# ddr3.net
KiCad netlist of a schematic drawn in Altium Designer
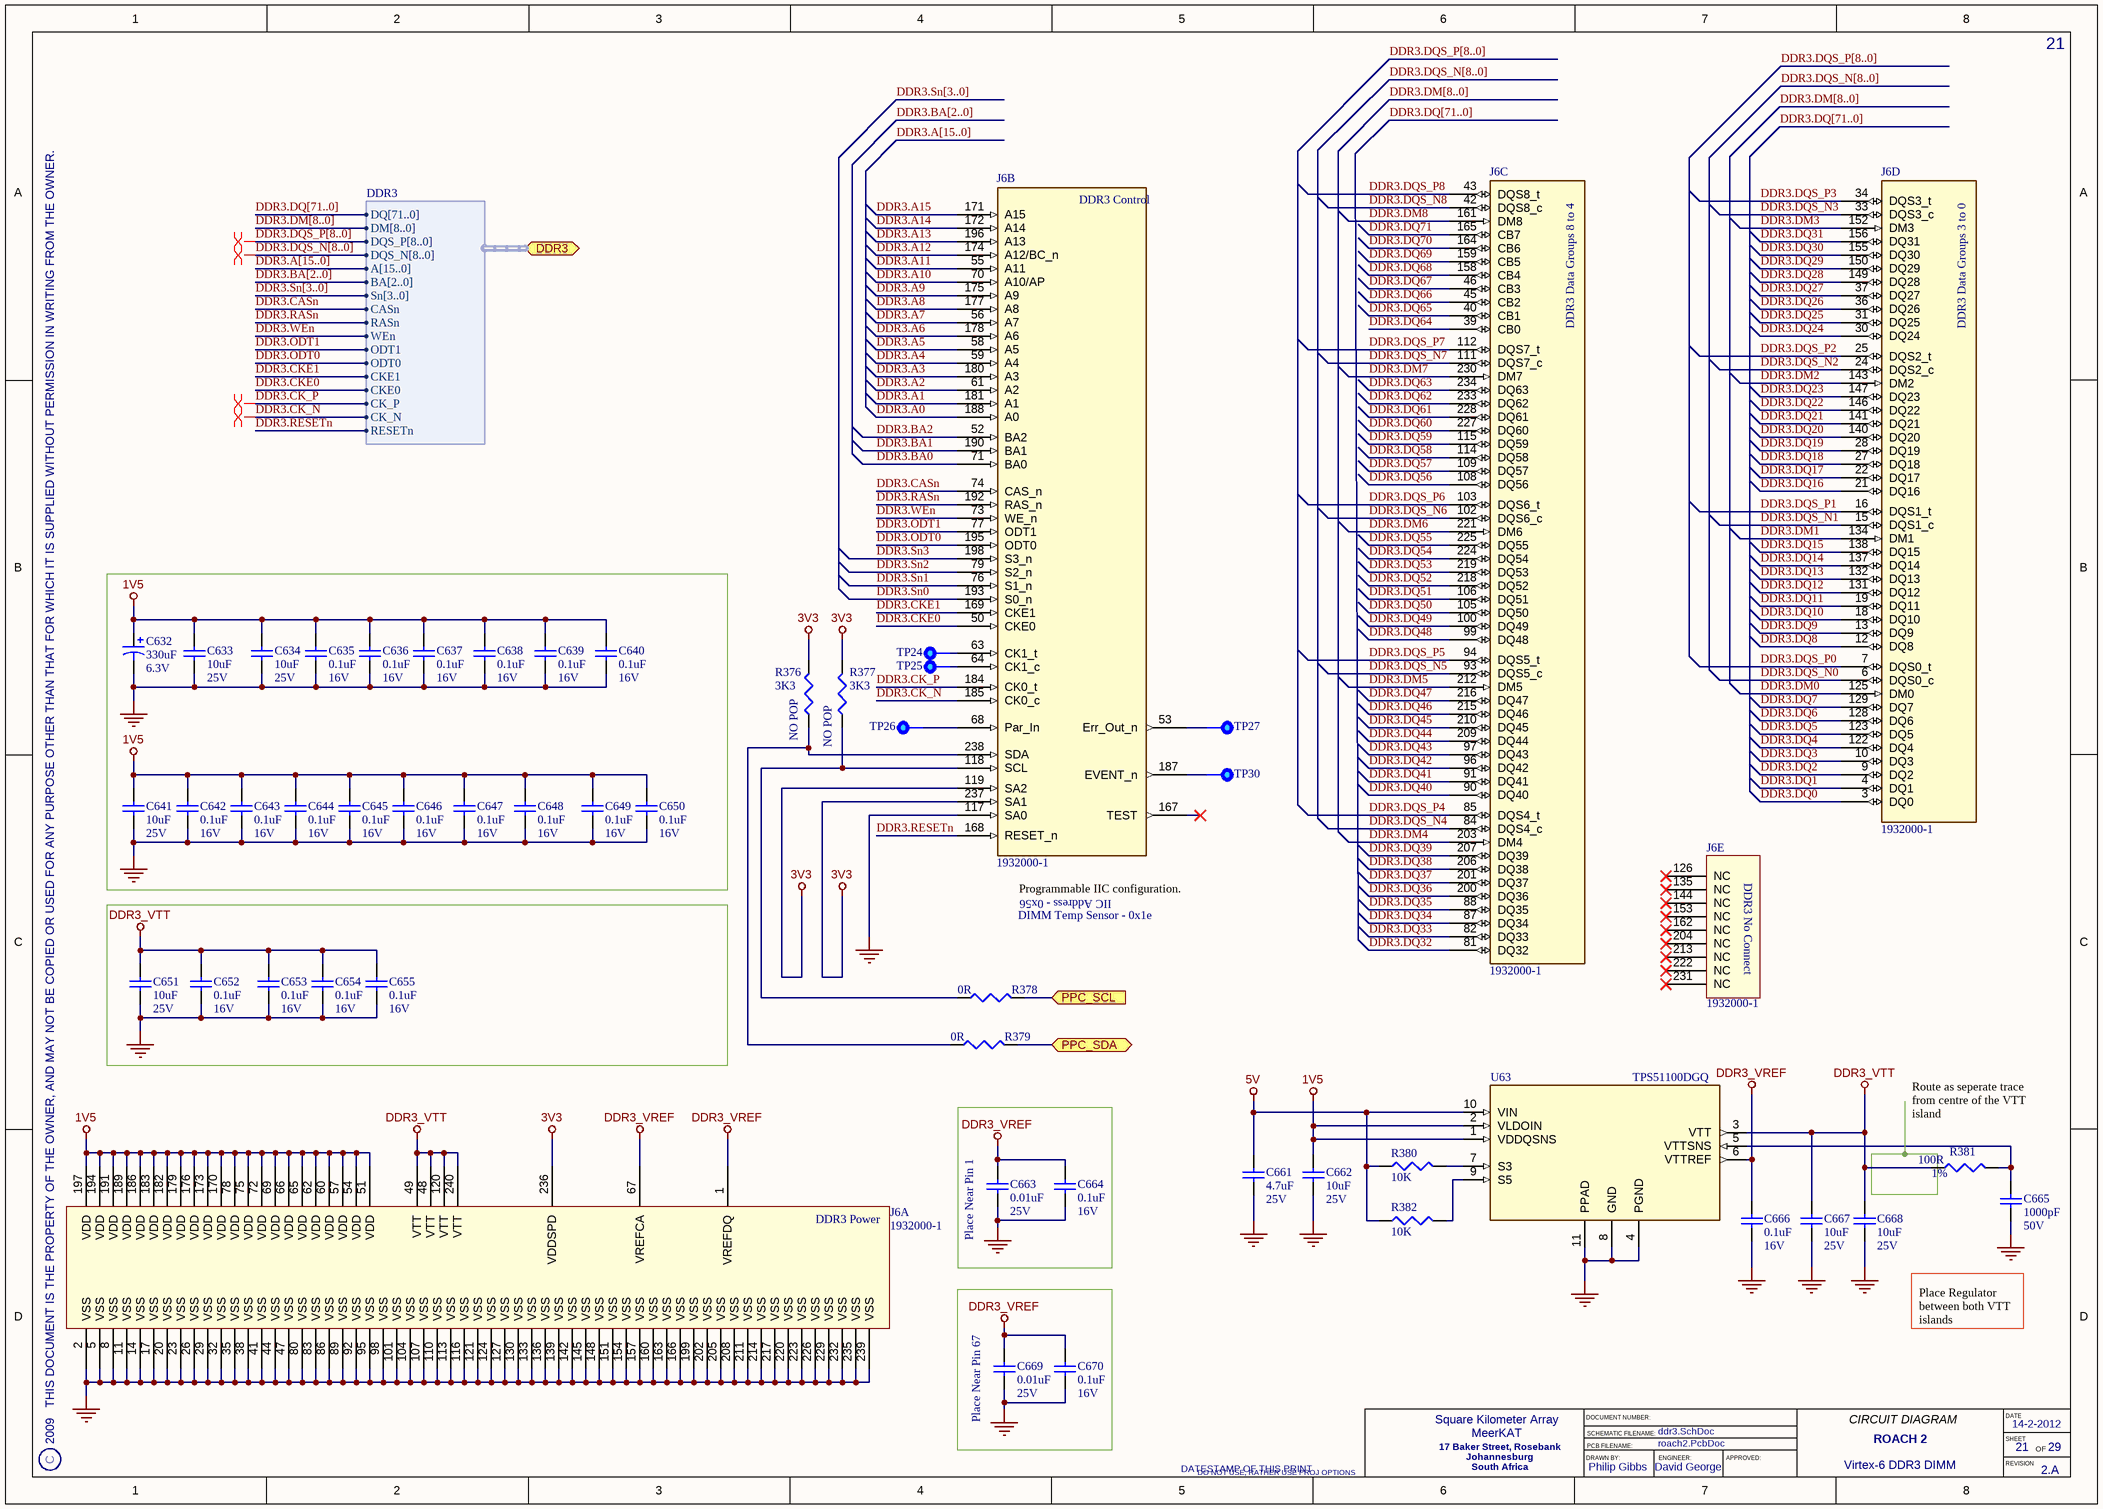
[diagram p0: ddr3.SchDoc]

(export (version "E")
  (design (tool "Eeschema 10.0.6"))
  (components
    (comp (ref "C632")
      (value "330uF")
      (footprint "CAPMP7343X280L")
      (description "330uF, Conductive Polymer Chip Capacitor")
      (fields
        (field (name "RATING") "6.3V")
        (field (name "MANUFACTURER") "KEMET")
        (field (name "PARTNUM") "T520D337M006ATE045")
      )
      (libsource (lib "altium_db") (part "CapPol"))
    )
    (comp (ref "C633")
      (value "10uF")
      (footprint "CAPC3225X200L")
      (description "10uF, Ceramic Capacitor")
      (fields
        (field (name "RATING") "25V")
        (field (name "MANUFACTURER") "MURATA")
        (field (name "PARTNUM") "GRM32DR61E106KA12L")
      )
      (libsource (lib "altium_db") (part "CapStd"))
    )
    (comp (ref "C634")
      (value "10uF")
      (footprint "CAPC3225X200L")
      (description "10uF, Ceramic Capacitor")
      (fields
        (field (name "RATING") "25V")
        (field (name "MANUFACTURER") "MURATA")
        (field (name "PARTNUM") "GRM32DR61E106KA12L")
      )
      (libsource (lib "altium_db") (part "CapStd"))
    )
    (comp (ref "C635")
      (value "0.1uF")
      (footprint "CAPC1005X60L")
      (description "0.1uF, Ceramic Capacitor")
      (fields
        (field (name "RATING") "16V")
        (field (name "MANUFACTURER") "VENKEL")
        (field (name "PARTNUM") "C0402X7R160-104KN")
      )
      (libsource (lib "altium_db") (part "CapStd"))
    )
    (comp (ref "C636")
      (value "0.1uF")
      (footprint "CAPC1005X60L")
      (description "0.1uF, Ceramic Capacitor")
      (fields
        (field (name "RATING") "16V")
        (field (name "MANUFACTURER") "VENKEL")
        (field (name "PARTNUM") "C0402X7R160-104KN")
      )
      (libsource (lib "altium_db") (part "CapStd"))
    )
    (comp (ref "C637")
      (value "0.1uF")
      (footprint "CAPC1005X60L")
      (description "0.1uF, Ceramic Capacitor")
      (fields
        (field (name "RATING") "16V")
        (field (name "MANUFACTURER") "VENKEL")
        (field (name "PARTNUM") "C0402X7R160-104KN")
      )
      (libsource (lib "altium_db") (part "CapStd"))
    )
    (comp (ref "C638")
      (value "0.1uF")
      (footprint "CAPC1005X60L")
      (description "0.1uF, Ceramic Capacitor")
      (fields
        (field (name "RATING") "16V")
        (field (name "MANUFACTURER") "VENKEL")
        (field (name "PARTNUM") "C0402X7R160-104KN")
      )
      (libsource (lib "altium_db") (part "CapStd"))
    )
    (comp (ref "C639")
      (value "0.1uF")
      (footprint "CAPC1005X60L")
      (description "0.1uF, Ceramic Capacitor")
      (fields
        (field (name "RATING") "16V")
        (field (name "MANUFACTURER") "VENKEL")
        (field (name "PARTNUM") "C0402X7R160-104KN")
      )
      (libsource (lib "altium_db") (part "CapStd"))
    )
    (comp (ref "C640")
      (value "0.1uF")
      (footprint "CAPC1005X60L")
      (description "0.1uF, Ceramic Capacitor")
      (fields
        (field (name "RATING") "16V")
        (field (name "MANUFACTURER") "VENKEL")
        (field (name "PARTNUM") "C0402X7R160-104KN")
      )
      (libsource (lib "altium_db") (part "CapStd"))
    )
    (comp (ref "C641")
      (value "10uF")
      (footprint "CAPC3225X200L")
      (description "10uF, Ceramic Capacitor")
      (fields
        (field (name "RATING") "25V")
        (field (name "MANUFACTURER") "MURATA")
        (field (name "PARTNUM") "GRM32DR61E106KA12L")
      )
      (libsource (lib "altium_db") (part "CapStd"))
    )
    (comp (ref "C642")
      (value "0.1uF")
      (footprint "CAPC1005X60L")
      (description "0.1uF, Ceramic Capacitor")
      (fields
        (field (name "RATING") "16V")
        (field (name "MANUFACTURER") "VENKEL")
        (field (name "PARTNUM") "C0402X7R160-104KN")
      )
      (libsource (lib "altium_db") (part "CapStd"))
    )
    (comp (ref "C643")
      (value "0.1uF")
      (footprint "CAPC1005X60L")
      (description "0.1uF, Ceramic Capacitor")
      (fields
        (field (name "RATING") "16V")
        (field (name "MANUFACTURER") "VENKEL")
        (field (name "PARTNUM") "C0402X7R160-104KN")
      )
      (libsource (lib "altium_db") (part "CapStd"))
    )
    (comp (ref "C644")
      (value "0.1uF")
      (footprint "CAPC1005X60L")
      (description "0.1uF, Ceramic Capacitor")
      (fields
        (field (name "RATING") "16V")
        (field (name "MANUFACTURER") "VENKEL")
        (field (name "PARTNUM") "C0402X7R160-104KN")
      )
      (libsource (lib "altium_db") (part "CapStd"))
    )
    (comp (ref "C645")
      (value "0.1uF")
      (footprint "CAPC1005X60L")
      (description "0.1uF, Ceramic Capacitor")
      (fields
        (field (name "RATING") "16V")
        (field (name "MANUFACTURER") "VENKEL")
        (field (name "PARTNUM") "C0402X7R160-104KN")
      )
      (libsource (lib "altium_db") (part "CapStd"))
    )
    (comp (ref "C646")
      (value "0.1uF")
      (footprint "CAPC1005X60L")
      (description "0.1uF, Ceramic Capacitor")
      (fields
        (field (name "RATING") "16V")
        (field (name "MANUFACTURER") "VENKEL")
        (field (name "PARTNUM") "C0402X7R160-104KN")
      )
      (libsource (lib "altium_db") (part "CapStd"))
    )
    (comp (ref "C647")
      (value "0.1uF")
      (footprint "CAPC1005X60L")
      (description "0.1uF, Ceramic Capacitor")
      (fields
        (field (name "RATING") "16V")
        (field (name "MANUFACTURER") "VENKEL")
        (field (name "PARTNUM") "C0402X7R160-104KN")
      )
      (libsource (lib "altium_db") (part "CapStd"))
    )
    (comp (ref "C648")
      (value "0.1uF")
      (footprint "CAPC1005X60L")
      (description "0.1uF, Ceramic Capacitor")
      (fields
        (field (name "RATING") "16V")
        (field (name "MANUFACTURER") "VENKEL")
        (field (name "PARTNUM") "C0402X7R160-104KN")
      )
      (libsource (lib "altium_db") (part "CapStd"))
    )
    (comp (ref "C649")
      (value "0.1uF")
      (footprint "CAPC1005X60L")
      (description "0.1uF, Ceramic Capacitor")
      (fields
        (field (name "RATING") "16V")
        (field (name "MANUFACTURER") "VENKEL")
        (field (name "PARTNUM") "C0402X7R160-104KN")
      )
      (libsource (lib "altium_db") (part "CapStd"))
    )
    (comp (ref "C650")
      (value "0.1uF")
      (footprint "CAPC1005X60L")
      (description "0.1uF, Ceramic Capacitor")
      (fields
        (field (name "RATING") "16V")
        (field (name "MANUFACTURER") "VENKEL")
        (field (name "PARTNUM") "C0402X7R160-104KN")
      )
      (libsource (lib "altium_db") (part "CapStd"))
    )
    (comp (ref "C651")
      (value "10uF")
      (footprint "CAPC3225X200L")
      (description "10uF, Ceramic Capacitor")
      (fields
        (field (name "RATING") "25V")
        (field (name "MANUFACTURER") "MURATA")
        (field (name "PARTNUM") "GRM32DR61E106KA12L")
      )
      (libsource (lib "altium_db") (part "CapStd"))
    )
    (comp (ref "C652")
      (value "0.1uF")
      (footprint "CAPC1005X60L")
      (description "0.1uF, Ceramic Capacitor")
      (fields
        (field (name "RATING") "16V")
        (field (name "MANUFACTURER") "VENKEL")
        (field (name "PARTNUM") "C0402X7R160-104KN")
      )
      (libsource (lib "altium_db") (part "CapStd"))
    )
    (comp (ref "C653")
      (value "0.1uF")
      (footprint "CAPC1005X60L")
      (description "0.1uF, Ceramic Capacitor")
      (fields
        (field (name "RATING") "16V")
        (field (name "MANUFACTURER") "VENKEL")
        (field (name "PARTNUM") "C0402X7R160-104KN")
      )
      (libsource (lib "altium_db") (part "CapStd"))
    )
    (comp (ref "C654")
      (value "0.1uF")
      (footprint "CAPC1005X60L")
      (description "0.1uF, Ceramic Capacitor")
      (fields
        (field (name "RATING") "16V")
        (field (name "MANUFACTURER") "VENKEL")
        (field (name "PARTNUM") "C0402X7R160-104KN")
      )
      (libsource (lib "altium_db") (part "CapStd"))
    )
    (comp (ref "C655")
      (value "0.1uF")
      (footprint "CAPC1005X60L")
      (description "0.1uF, Ceramic Capacitor")
      (fields
        (field (name "RATING") "16V")
        (field (name "MANUFACTURER") "VENKEL")
        (field (name "PARTNUM") "C0402X7R160-104KN")
      )
      (libsource (lib "altium_db") (part "CapStd"))
    )
    (comp (ref "C661")
      (value "4.7uF")
      (footprint "CAPC2012X127L")
      (description "4.7uF, Ceramic Capacitor")
      (fields
        (field (name "RATING") "25V")
        (field (name "MANUFACTURER") "MURATA")
        (field (name "PARTNUM") "GRM21BR61E475KA12K")
      )
      (libsource (lib "altium_db") (part "CapStd"))
    )
    (comp (ref "C662")
      (value "10uF")
      (footprint "CAPC3225X200L")
      (description "10uF, Ceramic Capacitor")
      (fields
        (field (name "RATING") "25V")
        (field (name "MANUFACTURER") "MURATA")
        (field (name "PARTNUM") "GRM32DR61E106KA12L")
      )
      (libsource (lib "altium_db") (part "CapStd"))
    )
    (comp (ref "C663")
      (value "0.01uF")
      (footprint "CAPC1005X55L")
      (description "0.01uF, Ceramic Capacitor")
      (fields
        (field (name "RATING") "25V")
        (field (name "MANUFACTURER") "MURATA")
        (field (name "PARTNUM") "GRM155R71E103KA01D")
      )
      (libsource (lib "altium_db") (part "CapStd"))
    )
    (comp (ref "C664")
      (value "0.1uF")
      (footprint "CAPC1005X60L")
      (description "0.1uF, Ceramic Capacitor")
      (fields
        (field (name "RATING") "16V")
        (field (name "MANUFACTURER") "VENKEL")
        (field (name "PARTNUM") "C0402X7R160-104KN")
      )
      (libsource (lib "altium_db") (part "CapStd"))
    )
    (comp (ref "C665")
      (value "1000pF")
      (footprint "CAPC1005X55L")
      (description "1000pF, Ceramic Capacitor")
      (fields
        (field (name "RATING") "50V")
        (field (name "MANUFACTURER") "MURATA")
        (field (name "PARTNUM") "GRM155R61H102KA01D")
      )
      (libsource (lib "altium_db") (part "CapStd"))
    )
    (comp (ref "C666")
      (value "0.1uF")
      (footprint "CAPC1005X60L")
      (description "0.1uF, Ceramic Capacitor")
      (fields
        (field (name "RATING") "16V")
        (field (name "MANUFACTURER") "VENKEL")
        (field (name "PARTNUM") "C0402X7R160-104KN")
      )
      (libsource (lib "altium_db") (part "CapStd"))
    )
    (comp (ref "C667")
      (value "10uF")
      (footprint "CAPC3225X200L")
      (description "10uF, Ceramic Capacitor")
      (fields
        (field (name "RATING") "25V")
        (field (name "MANUFACTURER") "MURATA")
        (field (name "PARTNUM") "GRM32DR61E106KA12L")
      )
      (libsource (lib "altium_db") (part "CapStd"))
    )
    (comp (ref "C668")
      (value "10uF")
      (footprint "CAPC3225X200L")
      (description "10uF, Ceramic Capacitor")
      (fields
        (field (name "RATING") "25V")
        (field (name "MANUFACTURER") "MURATA")
        (field (name "PARTNUM") "GRM32DR61E106KA12L")
      )
      (libsource (lib "altium_db") (part "CapStd"))
    )
    (comp (ref "C669")
      (value "0.01uF")
      (footprint "CAPC1005X55L")
      (description "0.01uF, Ceramic Capacitor")
      (fields
        (field (name "RATING") "25V")
        (field (name "MANUFACTURER") "MURATA")
        (field (name "PARTNUM") "GRM155R71E103KA01D")
      )
      (libsource (lib "altium_db") (part "CapStd"))
    )
    (comp (ref "C670")
      (value "0.1uF")
      (footprint "CAPC1005X60L")
      (description "0.1uF, Ceramic Capacitor")
      (fields
        (field (name "RATING") "16V")
        (field (name "MANUFACTURER") "VENKEL")
        (field (name "PARTNUM") "C0402X7R160-104KN")
      )
      (libsource (lib "altium_db") (part "CapStd"))
    )
    (comp (ref "J6")
      (value "1932000-1")
      (footprint "TYCO_1932000-1")
      (description "240-pin DDR3 DIMM Socket")
      (fields (field (name "PARTNUM") "1932000-1") (field (name "MANUFACTURER") "TYCO"))
      (libsource (lib "altium_db") (part "ddr3_dimm_240"))
    )
    (comp (ref "R376")
      (value "3K3")
      (footprint "RESC1005X40L")
      (description "3K3, 1.1mm x 0.5mm, Thick Film Resistor")
      (fields (field (name "MANUFACTURER") "ROYALOHM") (field (name "PARTNUM") "0402WGJ0332T1E"))
      (libsource (lib "altium_db") (part "ResStd"))
    )
    (comp (ref "R377")
      (value "3K3")
      (footprint "RESC1005X40L")
      (description "3K3, 1.1mm x 0.5mm, Thick Film Resistor")
      (fields (field (name "MANUFACTURER") "ROYALOHM") (field (name "PARTNUM") "0402WGJ0332T1E"))
      (libsource (lib "altium_db") (part "ResStd"))
    )
    (comp (ref "R378")
      (value "0R")
      (footprint "RESC1005X40L")
      (description "0R, 1.1mm x 0.5mm, Thick Film Resistor")
      (fields (field (name "MANUFACTURER") "ROYALOHM") (field (name "PARTNUM") "0402WG00000T1E"))
      (libsource (lib "Altium_DB") (part "ResStd"))
    )
    (comp (ref "R379")
      (value "0R")
      (footprint "RESC1005X40L")
      (description "0R, 1.1mm x 0.5mm, Thick Film Resistor")
      (fields (field (name "MANUFACTURER") "ROYALOHM") (field (name "PARTNUM") "0402WG00000T1E"))
      (libsource (lib "Altium_DB") (part "ResStd"))
    )
    (comp (ref "R380")
      (value "10K")
      (footprint "RESC1005X40L")
      (description "10K, 1.1mm x 0.5mm, Thick Film Resistor")
      (fields (field (name "MANUFACTURER") "ROYALOHM") (field (name "PARTNUM") "0402WGJ0103T1E"))
      (libsource (lib "altium_db") (part "ResStd"))
    )
    (comp (ref "R381")
      (value "100R")
      (footprint "RESC1005X40L")
      (description "100R, 1.1mm x 0.5mm, Thick Film Resistor")
      (fields
        (field (name "MANUFACTURER") "ROYALOHM")
        (field (name "PARTNUM") "0402WGF0101T1E")
        (field (name "TOLERANCE") "1%")
      )
      (libsource (lib "altium_db") (part "ResStd"))
    )
    (comp (ref "R382")
      (value "10K")
      (footprint "RESC1005X40L")
      (description "10K, 1.1mm x 0.5mm, Thick Film Resistor")
      (fields (field (name "MANUFACTURER") "ROYALOHM") (field (name "PARTNUM") "0402WGJ0103T1E"))
      (libsource (lib "altium_db") (part "ResStd"))
    )
    (comp (ref "TP24")
      (value "Testpoint")
      (footprint "TP100")
      (description "1mm Diameter, through-hole, Circular Test-point")
      (libsource (lib "altium_db") (part "Testpoint"))
    )
    (comp (ref "TP25")
      (value "Testpoint")
      (footprint "TP100")
      (description "1mm Diameter, through-hole, Circular Test-point")
      (libsource (lib "altium_db") (part "Testpoint"))
    )
    (comp (ref "TP26")
      (value "Testpoint")
      (footprint "TP100")
      (description "1mm Diameter, through-hole, Circular Test-point")
      (libsource (lib "altium_db") (part "Testpoint"))
    )
    (comp (ref "TP27")
      (value "Testpoint")
      (footprint "TP100")
      (description "1mm Diameter, through-hole, Circular Test-point")
      (libsource (lib "altium_db") (part "Testpoint"))
    )
    (comp (ref "TP30")
      (value "Testpoint")
      (footprint "TP100")
      (description "1mm Diameter, through-hole, Circular Test-point")
      (libsource (lib "altium_db") (part "Testpoint"))
    )
    (comp (ref "U63")
      (value "TPS51100DGQ")
      (footprint "MSOP_10-N")
      (description "3A Sink/Source Regulator")
      (fields (field (name "MANUFACTURER") "Texas Instruments"))
      (libsource (lib "altium_db") (part "TPS51100DGQ"))
    )
  )
  (nets
    (net (code "2") (name "/DDR3.A0") (class "Default")
      (node (ref "J6") (pin "188") (pinfunction "A0_188") (pintype "input"))
    )
    (net (code "3") (name "/DDR3.A1") (class "Default")
      (node (ref "J6") (pin "181") (pinfunction "A1_181") (pintype "input"))
    )
    (net (code "4") (name "/DDR3.A2") (class "Default")
      (node (ref "J6") (pin "61") (pinfunction "A2_61") (pintype "input"))
    )
    (net (code "5") (name "/DDR3.A3") (class "Default")
      (node (ref "J6") (pin "180") (pinfunction "A3_180") (pintype "input"))
    )
    (net (code "6") (name "/DDR3.A4") (class "Default")
      (node (ref "J6") (pin "59") (pinfunction "A4_59") (pintype "input"))
    )
    (net (code "7") (name "/DDR3.A5") (class "Default")
      (node (ref "J6") (pin "58") (pinfunction "A5_58") (pintype "input"))
    )
    (net (code "8") (name "/DDR3.A6") (class "Default")
      (node (ref "J6") (pin "178") (pinfunction "A6_178") (pintype "input"))
    )
    (net (code "9") (name "/DDR3.A7") (class "Default")
      (node (ref "J6") (pin "56") (pinfunction "A7_56") (pintype "input"))
    )
    (net (code "10") (name "/DDR3.A8") (class "Default")
      (node (ref "J6") (pin "177") (pinfunction "A8_177") (pintype "input"))
    )
    (net (code "11") (name "/DDR3.A9") (class "Default")
      (node (ref "J6") (pin "175") (pinfunction "A9_175") (pintype "input"))
    )
    (net (code "12") (name "/DDR3.A10") (class "Default")
      (node (ref "J6") (pin "70") (pinfunction "A10/AP_70") (pintype "input"))
    )
    (net (code "13") (name "/DDR3.A11") (class "Default")
      (node (ref "J6") (pin "55") (pinfunction "A11_55") (pintype "input"))
    )
    (net (code "14") (name "/DDR3.A12") (class "Default")
      (node (ref "J6") (pin "174") (pinfunction "A12/BC_n_174") (pintype "input"))
    )
    (net (code "15") (name "/DDR3.A13") (class "Default")
      (node (ref "J6") (pin "196") (pinfunction "A13_196") (pintype "input"))
    )
    (net (code "16") (name "/DDR3.A14") (class "Default")
      (node (ref "J6") (pin "172") (pinfunction "A14_172") (pintype "input"))
    )
    (net (code "17") (name "/DDR3.A15") (class "Default")
      (node (ref "J6") (pin "171") (pinfunction "A15_171") (pintype "input"))
    )
    (net (code "19") (name "/DDR3.BA0") (class "Default")
      (node (ref "J6") (pin "71") (pinfunction "BA0_71") (pintype "input"))
    )
    (net (code "20") (name "/DDR3.BA1") (class "Default")
      (node (ref "J6") (pin "190") (pinfunction "BA1_190") (pintype "input"))
    )
    (net (code "21") (name "/DDR3.BA2") (class "Default")
      (node (ref "J6") (pin "52") (pinfunction "BA2_52") (pintype "input"))
    )
    (net (code "23") (name "/DDR3.CASn") (class "Default")
      (node (ref "J6") (pin "74") (pinfunction "CAS_n_74") (pintype "input"))
    )
    (net (code "24") (name "/DDR3.CKE0") (class "Default")
      (node (ref "J6") (pin "50") (pinfunction "CKE0_50") (pintype "input"))
    )
    (net (code "25") (name "/DDR3.CKE1") (class "Default")
      (node (ref "J6") (pin "169") (pinfunction "CKE1_169") (pintype "input"))
    )
    (net (code "26") (name "/DDR3.CK_N") (class "Default")
      (node (ref "J6") (pin "185") (pinfunction "CK0_c_185") (pintype "input"))
    )
    (net (code "27") (name "/DDR3.CK_P") (class "Default")
      (node (ref "J6") (pin "184") (pinfunction "CK0_t_184") (pintype "input"))
    )
    (net (code "28") (name "/DDR3.DM0") (class "Default")
      (node (ref "J6") (pin "125") (pinfunction "DM0_125") (pintype "input"))
    )
    (net (code "29") (name "/DDR3.DM1") (class "Default")
      (node (ref "J6") (pin "134") (pinfunction "DM1_134") (pintype "input"))
    )
    (net (code "30") (name "/DDR3.DM2") (class "Default")
      (node (ref "J6") (pin "143") (pinfunction "DM2_143") (pintype "input"))
    )
    (net (code "31") (name "/DDR3.DM3") (class "Default")
      (node (ref "J6") (pin "152") (pinfunction "DM3_152") (pintype "input"))
    )
    (net (code "32") (name "/DDR3.DM4") (class "Default")
      (node (ref "J6") (pin "203") (pinfunction "DM4_203") (pintype "input"))
    )
    (net (code "33") (name "/DDR3.DM5") (class "Default")
      (node (ref "J6") (pin "212") (pinfunction "DM5_212") (pintype "input"))
    )
    (net (code "34") (name "/DDR3.DM6") (class "Default")
      (node (ref "J6") (pin "221") (pinfunction "DM6_221") (pintype "input"))
    )
    (net (code "35") (name "/DDR3.DM7") (class "Default")
      (node (ref "J6") (pin "230") (pinfunction "DM7_230") (pintype "input"))
    )
    (net (code "36") (name "/DDR3.DM8") (class "Default")
      (node (ref "J6") (pin "161") (pinfunction "DM8_161") (pintype "input"))
    )
    (net (code "38") (name "/DDR3.DQ0") (class "Default")
      (node (ref "J6") (pin "3") (pinfunction "DQ0_3") (pintype "bidirectional"))
    )
    (net (code "39") (name "/DDR3.DQ1") (class "Default")
      (node (ref "J6") (pin "4") (pinfunction "DQ1_4") (pintype "bidirectional"))
    )
    (net (code "40") (name "/DDR3.DQ2") (class "Default")
      (node (ref "J6") (pin "9") (pinfunction "DQ2_9") (pintype "bidirectional"))
    )
    (net (code "41") (name "/DDR3.DQ3") (class "Default")
      (node (ref "J6") (pin "10") (pinfunction "DQ3_10") (pintype "bidirectional"))
    )
    (net (code "42") (name "/DDR3.DQ4") (class "Default")
      (node (ref "J6") (pin "122") (pinfunction "DQ4_122") (pintype "bidirectional"))
    )
    (net (code "43") (name "/DDR3.DQ5") (class "Default")
      (node (ref "J6") (pin "123") (pinfunction "DQ5_123") (pintype "bidirectional"))
    )
    (net (code "44") (name "/DDR3.DQ6") (class "Default")
      (node (ref "J6") (pin "128") (pinfunction "DQ6_128") (pintype "bidirectional"))
    )
    (net (code "45") (name "/DDR3.DQ7") (class "Default")
      (node (ref "J6") (pin "129") (pinfunction "DQ7_129") (pintype "bidirectional"))
    )
    (net (code "46") (name "/DDR3.DQ8") (class "Default")
      (node (ref "J6") (pin "12") (pinfunction "DQ8_12") (pintype "bidirectional"))
    )
    (net (code "47") (name "/DDR3.DQ9") (class "Default")
      (node (ref "J6") (pin "13") (pinfunction "DQ9_13") (pintype "bidirectional"))
    )
    (net (code "48") (name "/DDR3.DQ10") (class "Default")
      (node (ref "J6") (pin "18") (pinfunction "DQ10_18") (pintype "bidirectional"))
    )
    (net (code "49") (name "/DDR3.DQ11") (class "Default")
      (node (ref "J6") (pin "19") (pinfunction "DQ11_19") (pintype "bidirectional"))
    )
    (net (code "50") (name "/DDR3.DQ12") (class "Default")
      (node (ref "J6") (pin "131") (pinfunction "DQ12_131") (pintype "bidirectional"))
    )
    (net (code "51") (name "/DDR3.DQ13") (class "Default")
      (node (ref "J6") (pin "132") (pinfunction "DQ13_132") (pintype "bidirectional"))
    )
    (net (code "52") (name "/DDR3.DQ14") (class "Default")
      (node (ref "J6") (pin "137") (pinfunction "DQ14_137") (pintype "bidirectional"))
    )
    (net (code "53") (name "/DDR3.DQ15") (class "Default")
      (node (ref "J6") (pin "138") (pinfunction "DQ15_138") (pintype "bidirectional"))
    )
    (net (code "54") (name "/DDR3.DQ16") (class "Default")
      (node (ref "J6") (pin "21") (pinfunction "DQ16_21") (pintype "bidirectional"))
    )
    (net (code "55") (name "/DDR3.DQ17") (class "Default")
      (node (ref "J6") (pin "22") (pinfunction "DQ17_22") (pintype "bidirectional"))
    )
    (net (code "56") (name "/DDR3.DQ18") (class "Default")
      (node (ref "J6") (pin "27") (pinfunction "DQ18_27") (pintype "bidirectional"))
    )
    (net (code "57") (name "/DDR3.DQ19") (class "Default")
      (node (ref "J6") (pin "28") (pinfunction "DQ19_28") (pintype "bidirectional"))
    )
    (net (code "58") (name "/DDR3.DQ20") (class "Default")
      (node (ref "J6") (pin "140") (pinfunction "DQ20_140") (pintype "bidirectional"))
    )
    (net (code "59") (name "/DDR3.DQ21") (class "Default")
      (node (ref "J6") (pin "141") (pinfunction "DQ21_141") (pintype "bidirectional"))
    )
    (net (code "60") (name "/DDR3.DQ22") (class "Default")
      (node (ref "J6") (pin "146") (pinfunction "DQ22_146") (pintype "bidirectional"))
    )
    (net (code "61") (name "/DDR3.DQ23") (class "Default")
      (node (ref "J6") (pin "147") (pinfunction "DQ23_147") (pintype "bidirectional"))
    )
    (net (code "62") (name "/DDR3.DQ24") (class "Default")
      (node (ref "J6") (pin "30") (pinfunction "DQ24_30") (pintype "bidirectional"))
    )
    (net (code "63") (name "/DDR3.DQ25") (class "Default")
      (node (ref "J6") (pin "31") (pinfunction "DQ25_31") (pintype "bidirectional"))
    )
    (net (code "64") (name "/DDR3.DQ26") (class "Default")
      (node (ref "J6") (pin "36") (pinfunction "DQ26_36") (pintype "bidirectional"))
    )
    (net (code "65") (name "/DDR3.DQ27") (class "Default")
      (node (ref "J6") (pin "37") (pinfunction "DQ27_37") (pintype "bidirectional"))
    )
    (net (code "66") (name "/DDR3.DQ28") (class "Default")
      (node (ref "J6") (pin "149") (pinfunction "DQ28_149") (pintype "bidirectional"))
    )
    (net (code "67") (name "/DDR3.DQ29") (class "Default")
      (node (ref "J6") (pin "150") (pinfunction "DQ29_150") (pintype "bidirectional"))
    )
    (net (code "68") (name "/DDR3.DQ30") (class "Default")
      (node (ref "J6") (pin "155") (pinfunction "DQ30_155") (pintype "bidirectional"))
    )
    (net (code "69") (name "/DDR3.DQ31") (class "Default")
      (node (ref "J6") (pin "156") (pinfunction "DQ31_156") (pintype "bidirectional"))
    )
    (net (code "70") (name "/DDR3.DQ32") (class "Default")
      (node (ref "J6") (pin "81") (pinfunction "DQ32_81") (pintype "bidirectional"))
    )
    (net (code "71") (name "/DDR3.DQ33") (class "Default")
      (node (ref "J6") (pin "82") (pinfunction "DQ33_82") (pintype "bidirectional"))
    )
    (net (code "72") (name "/DDR3.DQ34") (class "Default")
      (node (ref "J6") (pin "87") (pinfunction "DQ34_87") (pintype "bidirectional"))
    )
    (net (code "73") (name "/DDR3.DQ35") (class "Default")
      (node (ref "J6") (pin "88") (pinfunction "DQ35_88") (pintype "bidirectional"))
    )
    (net (code "74") (name "/DDR3.DQ36") (class "Default")
      (node (ref "J6") (pin "200") (pinfunction "DQ36_200") (pintype "bidirectional"))
    )
    (net (code "75") (name "/DDR3.DQ37") (class "Default")
      (node (ref "J6") (pin "201") (pinfunction "DQ37_201") (pintype "bidirectional"))
    )
    (net (code "76") (name "/DDR3.DQ38") (class "Default")
      (node (ref "J6") (pin "206") (pinfunction "DQ38_206") (pintype "bidirectional"))
    )
    (net (code "77") (name "/DDR3.DQ39") (class "Default")
      (node (ref "J6") (pin "207") (pinfunction "DQ39_207") (pintype "bidirectional"))
    )
    (net (code "78") (name "/DDR3.DQ40") (class "Default")
      (node (ref "J6") (pin "90") (pinfunction "DQ40_90") (pintype "bidirectional"))
    )
    (net (code "79") (name "/DDR3.DQ41") (class "Default")
      (node (ref "J6") (pin "91") (pinfunction "DQ41_91") (pintype "bidirectional"))
    )
    (net (code "80") (name "/DDR3.DQ42") (class "Default")
      (node (ref "J6") (pin "96") (pinfunction "DQ42_96") (pintype "bidirectional"))
    )
    (net (code "81") (name "/DDR3.DQ43") (class "Default")
      (node (ref "J6") (pin "97") (pinfunction "DQ43_97") (pintype "bidirectional"))
    )
    (net (code "82") (name "/DDR3.DQ44") (class "Default")
      (node (ref "J6") (pin "209") (pinfunction "DQ44_209") (pintype "bidirectional"))
    )
    (net (code "83") (name "/DDR3.DQ45") (class "Default")
      (node (ref "J6") (pin "210") (pinfunction "DQ45_210") (pintype "bidirectional"))
    )
    (net (code "84") (name "/DDR3.DQ46") (class "Default")
      (node (ref "J6") (pin "215") (pinfunction "DQ46_215") (pintype "bidirectional"))
    )
    (net (code "85") (name "/DDR3.DQ47") (class "Default")
      (node (ref "J6") (pin "216") (pinfunction "DQ47_216") (pintype "bidirectional"))
    )
    (net (code "86") (name "/DDR3.DQ48") (class "Default")
      (node (ref "J6") (pin "99") (pinfunction "DQ48_99") (pintype "bidirectional"))
    )
    (net (code "87") (name "/DDR3.DQ49") (class "Default")
      (node (ref "J6") (pin "100") (pinfunction "DQ49_100") (pintype "bidirectional"))
    )
    (net (code "88") (name "/DDR3.DQ50") (class "Default")
      (node (ref "J6") (pin "105") (pinfunction "DQ50_105") (pintype "bidirectional"))
    )
    (net (code "89") (name "/DDR3.DQ51") (class "Default")
      (node (ref "J6") (pin "106") (pinfunction "DQ51_106") (pintype "bidirectional"))
    )
    (net (code "90") (name "/DDR3.DQ52") (class "Default")
      (node (ref "J6") (pin "218") (pinfunction "DQ52_218") (pintype "bidirectional"))
    )
    (net (code "91") (name "/DDR3.DQ53") (class "Default")
      (node (ref "J6") (pin "219") (pinfunction "DQ53_219") (pintype "bidirectional"))
    )
    (net (code "92") (name "/DDR3.DQ54") (class "Default")
      (node (ref "J6") (pin "224") (pinfunction "DQ54_224") (pintype "bidirectional"))
    )
    (net (code "93") (name "/DDR3.DQ55") (class "Default")
      (node (ref "J6") (pin "225") (pinfunction "DQ55_225") (pintype "bidirectional"))
    )
    (net (code "94") (name "/DDR3.DQ56") (class "Default")
      (node (ref "J6") (pin "108") (pinfunction "DQ56_108") (pintype "bidirectional"))
    )
    (net (code "95") (name "/DDR3.DQ57") (class "Default")
      (node (ref "J6") (pin "109") (pinfunction "DQ57_109") (pintype "bidirectional"))
    )
    (net (code "96") (name "/DDR3.DQ58") (class "Default")
      (node (ref "J6") (pin "114") (pinfunction "DQ58_114") (pintype "bidirectional"))
    )
    (net (code "97") (name "/DDR3.DQ59") (class "Default")
      (node (ref "J6") (pin "115") (pinfunction "DQ59_115") (pintype "bidirectional"))
    )
    (net (code "98") (name "/DDR3.DQ60") (class "Default")
      (node (ref "J6") (pin "227") (pinfunction "DQ60_227") (pintype "bidirectional"))
    )
    (net (code "99") (name "/DDR3.DQ61") (class "Default")
      (node (ref "J6") (pin "228") (pinfunction "DQ61_228") (pintype "bidirectional"))
    )
    (net (code "100") (name "/DDR3.DQ62") (class "Default")
      (node (ref "J6") (pin "233") (pinfunction "DQ62_233") (pintype "bidirectional"))
    )
    (net (code "101") (name "/DDR3.DQ63") (class "Default")
      (node (ref "J6") (pin "234") (pinfunction "DQ63_234") (pintype "bidirectional"))
    )
    (net (code "102") (name "/DDR3.DQ64") (class "Default")
      (node (ref "J6") (pin "39") (pinfunction "CB0_39") (pintype "bidirectional"))
    )
    (net (code "103") (name "/DDR3.DQ65") (class "Default")
      (node (ref "J6") (pin "40") (pinfunction "CB1_40") (pintype "bidirectional"))
    )
    (net (code "104") (name "/DDR3.DQ66") (class "Default")
      (node (ref "J6") (pin "45") (pinfunction "CB2_45") (pintype "bidirectional"))
    )
    (net (code "105") (name "/DDR3.DQ67") (class "Default")
      (node (ref "J6") (pin "46") (pinfunction "CB3_46") (pintype "bidirectional"))
    )
    (net (code "106") (name "/DDR3.DQ68") (class "Default")
      (node (ref "J6") (pin "158") (pinfunction "CB4_158") (pintype "bidirectional"))
    )
    (net (code "107") (name "/DDR3.DQ69") (class "Default")
      (node (ref "J6") (pin "159") (pinfunction "CB5_159") (pintype "bidirectional"))
    )
    (net (code "108") (name "/DDR3.DQ70") (class "Default")
      (node (ref "J6") (pin "164") (pinfunction "CB6_164") (pintype "bidirectional"))
    )
    (net (code "109") (name "/DDR3.DQ71") (class "Default")
      (node (ref "J6") (pin "165") (pinfunction "CB7_165") (pintype "bidirectional"))
    )
    (net (code "110") (name "/DDR3.DQS_N0") (class "Default")
      (node (ref "J6") (pin "6") (pinfunction "DQS0_c_6") (pintype "bidirectional"))
    )
    (net (code "111") (name "/DDR3.DQS_N1") (class "Default")
      (node (ref "J6") (pin "15") (pinfunction "DQS1_c_15") (pintype "bidirectional"))
    )
    (net (code "112") (name "/DDR3.DQS_N2") (class "Default")
      (node (ref "J6") (pin "24") (pinfunction "DQS2_c_24") (pintype "bidirectional"))
    )
    (net (code "113") (name "/DDR3.DQS_N3") (class "Default")
      (node (ref "J6") (pin "33") (pinfunction "DQS3_c_33") (pintype "bidirectional"))
    )
    (net (code "114") (name "/DDR3.DQS_N4") (class "Default")
      (node (ref "J6") (pin "84") (pinfunction "DQS4_c_84") (pintype "bidirectional"))
    )
    (net (code "115") (name "/DDR3.DQS_N5") (class "Default")
      (node (ref "J6") (pin "93") (pinfunction "DQS5_c_93") (pintype "bidirectional"))
    )
    (net (code "116") (name "/DDR3.DQS_N6") (class "Default")
      (node (ref "J6") (pin "102") (pinfunction "DQS6_c_102") (pintype "bidirectional"))
    )
    (net (code "117") (name "/DDR3.DQS_N7") (class "Default")
      (node (ref "J6") (pin "111") (pinfunction "DQS7_c_111") (pintype "bidirectional"))
    )
    (net (code "118") (name "/DDR3.DQS_N8") (class "Default")
      (node (ref "J6") (pin "42") (pinfunction "DQS8_c_42") (pintype "bidirectional"))
    )
    (net (code "120") (name "/DDR3.DQS_P0") (class "Default")
      (node (ref "J6") (pin "7") (pinfunction "DQS0_t_7") (pintype "bidirectional"))
    )
    (net (code "121") (name "/DDR3.DQS_P1") (class "Default")
      (node (ref "J6") (pin "16") (pinfunction "DQS1_t_16") (pintype "bidirectional"))
    )
    (net (code "122") (name "/DDR3.DQS_P2") (class "Default")
      (node (ref "J6") (pin "25") (pinfunction "DQS2_t_25") (pintype "bidirectional"))
    )
    (net (code "123") (name "/DDR3.DQS_P3") (class "Default")
      (node (ref "J6") (pin "34") (pinfunction "DQS3_t_34") (pintype "bidirectional"))
    )
    (net (code "124") (name "/DDR3.DQS_P4") (class "Default")
      (node (ref "J6") (pin "85") (pinfunction "DQS4_t_85") (pintype "bidirectional"))
    )
    (net (code "125") (name "/DDR3.DQS_P5") (class "Default")
      (node (ref "J6") (pin "94") (pinfunction "DQS5_t_94") (pintype "bidirectional"))
    )
    (net (code "126") (name "/DDR3.DQS_P6") (class "Default")
      (node (ref "J6") (pin "103") (pinfunction "DQS6_t_103") (pintype "bidirectional"))
    )
    (net (code "127") (name "/DDR3.DQS_P7") (class "Default")
      (node (ref "J6") (pin "112") (pinfunction "DQS7_t_112") (pintype "bidirectional"))
    )
    (net (code "128") (name "/DDR3.DQS_P8") (class "Default")
      (node (ref "J6") (pin "43") (pinfunction "DQS8_t_43") (pintype "bidirectional"))
    )
    (net (code "131") (name "/DDR3.ODT0") (class "Default")
      (node (ref "J6") (pin "195") (pinfunction "ODT0_195") (pintype "input"))
    )
    (net (code "132") (name "/DDR3.ODT1") (class "Default")
      (node (ref "J6") (pin "77") (pinfunction "ODT1_77") (pintype "input"))
    )
    (net (code "133") (name "/DDR3.RASn") (class "Default")
      (node (ref "J6") (pin "192") (pinfunction "RAS_n_192") (pintype "input"))
    )
    (net (code "134") (name "/DDR3.RESETn") (class "Default")
      (node (ref "J6") (pin "168") (pinfunction "RESET_n_168") (pintype "input"))
    )
    (net (code "135") (name "/DDR3.Sn0") (class "Default")
      (node (ref "J6") (pin "193") (pinfunction "S0_n_193") (pintype "input"))
    )
    (net (code "136") (name "/DDR3.Sn1") (class "Default")
      (node (ref "J6") (pin "76") (pinfunction "S1_n_76") (pintype "input"))
    )
    (net (code "137") (name "/DDR3.Sn2") (class "Default")
      (node (ref "J6") (pin "79") (pinfunction "S2_n_79") (pintype "input"))
    )
    (net (code "138") (name "/DDR3.Sn3") (class "Default")
      (node (ref "J6") (pin "198") (pinfunction "S3_n_198") (pintype "input"))
    )
    (net (code "140") (name "/DDR3.WEn") (class "Default")
      (node (ref "J6") (pin "73") (pinfunction "WE_n_73") (pintype "input"))
    )
    (net (code "141") (name "/PPC_SCL") (class "Default")
      (node (ref "R378") (pin "2") (pinfunction "2_2") (pintype "passive"))
    )
    (net (code "142") (name "/PPC_SDA") (class "Default")
      (node (ref "R379") (pin "2") (pinfunction "2_2") (pintype "passive"))
    )
    (net (code "144") (name "1V5") (class "Default")
      (node (ref "C632") (pin "1") (pinfunction "1_1") (pintype "passive"))
      (node (ref "C633") (pin "2") (pinfunction "2_2") (pintype "passive"))
      (node (ref "C634") (pin "2") (pinfunction "2_2") (pintype "passive"))
      (node (ref "C635") (pin "2") (pinfunction "2_2") (pintype "passive"))
      (node (ref "C636") (pin "2") (pinfunction "2_2") (pintype "passive"))
      (node (ref "C637") (pin "2") (pinfunction "2_2") (pintype "passive"))
      (node (ref "C638") (pin "2") (pinfunction "2_2") (pintype "passive"))
      (node (ref "C639") (pin "2") (pinfunction "2_2") (pintype "passive"))
      (node (ref "C640") (pin "2") (pinfunction "2_2") (pintype "passive"))
      (node (ref "C641") (pin "2") (pinfunction "2_2") (pintype "passive"))
      (node (ref "C642") (pin "2") (pinfunction "2_2") (pintype "passive"))
      (node (ref "C643") (pin "2") (pinfunction "2_2") (pintype "passive"))
      (node (ref "C644") (pin "2") (pinfunction "2_2") (pintype "passive"))
      (node (ref "C645") (pin "2") (pinfunction "2_2") (pintype "passive"))
      (node (ref "C646") (pin "2") (pinfunction "2_2") (pintype "passive"))
      (node (ref "C647") (pin "2") (pinfunction "2_2") (pintype "passive"))
      (node (ref "C648") (pin "2") (pinfunction "2_2") (pintype "passive"))
      (node (ref "C649") (pin "2") (pinfunction "2_2") (pintype "passive"))
      (node (ref "C650") (pin "2") (pinfunction "2_2") (pintype "passive"))
      (node (ref "C662") (pin "2") (pinfunction "2_2") (pintype "passive"))
      (node (ref "J6") (pin "170") (pinfunction "VDD_170") (pintype "passive"))
      (node (ref "J6") (pin "173") (pinfunction "VDD_173") (pintype "passive"))
      (node (ref "J6") (pin "176") (pinfunction "VDD_176") (pintype "passive"))
      (node (ref "J6") (pin "179") (pinfunction "VDD_179") (pintype "passive"))
      (node (ref "J6") (pin "182") (pinfunction "VDD_182") (pintype "passive"))
      (node (ref "J6") (pin "183") (pinfunction "VDD_183") (pintype "passive"))
      (node (ref "J6") (pin "186") (pinfunction "VDD_186") (pintype "passive"))
      (node (ref "J6") (pin "189") (pinfunction "VDD_189") (pintype "passive"))
      (node (ref "J6") (pin "191") (pinfunction "VDD_191") (pintype "passive"))
      (node (ref "J6") (pin "194") (pinfunction "VDD_194") (pintype "passive"))
      (node (ref "J6") (pin "197") (pinfunction "VDD_197") (pintype "passive"))
      (node (ref "J6") (pin "51") (pinfunction "VDD_51") (pintype "passive"))
      (node (ref "J6") (pin "54") (pinfunction "VDD_54") (pintype "passive"))
      (node (ref "J6") (pin "57") (pinfunction "VDD_57") (pintype "passive"))
      (node (ref "J6") (pin "60") (pinfunction "VDD_60") (pintype "passive"))
      (node (ref "J6") (pin "62") (pinfunction "VDD_62") (pintype "passive"))
      (node (ref "J6") (pin "65") (pinfunction "VDD_65") (pintype "passive"))
      (node (ref "J6") (pin "66") (pinfunction "VDD_66") (pintype "passive"))
      (node (ref "J6") (pin "69") (pinfunction "VDD_69") (pintype "passive"))
      (node (ref "J6") (pin "72") (pinfunction "VDD_72") (pintype "passive"))
      (node (ref "J6") (pin "75") (pinfunction "VDD_75") (pintype "passive"))
      (node (ref "J6") (pin "78") (pinfunction "VDD_78") (pintype "passive"))
      (node (ref "U63") (pin "1") (pinfunction "VDDQSNS_1") (pintype "input"))
      (node (ref "U63") (pin "2") (pinfunction "VLDOIN_2") (pintype "input"))
    )
    (net (code "145") (name "3V3") (class "Default")
      (node (ref "J6") (pin "119") (pinfunction "SA2_119") (pintype "input"))
      (node (ref "J6") (pin "236") (pinfunction "VDDSPD_236") (pintype "passive"))
      (node (ref "J6") (pin "237") (pinfunction "SA1_237") (pintype "input"))
      (node (ref "R376") (pin "2") (pinfunction "2_2") (pintype "passive"))
      (node (ref "R377") (pin "2") (pinfunction "2_2") (pintype "passive"))
    )
    (net (code "146") (name "5V") (class "Default")
      (node (ref "C661") (pin "2") (pinfunction "2_2") (pintype "passive"))
      (node (ref "R380") (pin "1") (pinfunction "1_1") (pintype "passive"))
      (node (ref "R382") (pin "1") (pinfunction "1_1") (pintype "passive"))
      (node (ref "U63") (pin "10") (pinfunction "VIN_10") (pintype "input"))
    )
    (net (code "147") (name "DDR3_VREF") (class "Default")
      (node (ref "C663") (pin "2") (pinfunction "2_2") (pintype "passive"))
      (node (ref "C664") (pin "2") (pinfunction "2_2") (pintype "passive"))
      (node (ref "C666") (pin "2") (pinfunction "2_2") (pintype "passive"))
      (node (ref "C669") (pin "2") (pinfunction "2_2") (pintype "passive"))
      (node (ref "C670") (pin "2") (pinfunction "2_2") (pintype "passive"))
      (node (ref "J6") (pin "1") (pinfunction "VREFDQ_1") (pintype "passive"))
      (node (ref "J6") (pin "67") (pinfunction "VREFCA_67") (pintype "passive"))
      (node (ref "U63") (pin "6") (pinfunction "VTTREF_6") (pintype "output"))
    )
    (net (code "148") (name "DDR3_VTT") (class "Default")
      (node (ref "C651") (pin "2") (pinfunction "2_2") (pintype "passive"))
      (node (ref "C652") (pin "2") (pinfunction "2_2") (pintype "passive"))
      (node (ref "C653") (pin "2") (pinfunction "2_2") (pintype "passive"))
      (node (ref "C654") (pin "2") (pinfunction "2_2") (pintype "passive"))
      (node (ref "C655") (pin "2") (pinfunction "2_2") (pintype "passive"))
      (node (ref "C667") (pin "2") (pinfunction "2_2") (pintype "passive"))
      (node (ref "C668") (pin "2") (pinfunction "2_2") (pintype "passive"))
      (node (ref "J6") (pin "120") (pinfunction "VTT_120") (pintype "passive"))
      (node (ref "J6") (pin "240") (pinfunction "VTT_240") (pintype "passive"))
      (node (ref "J6") (pin "48") (pinfunction "VTT_48") (pintype "passive"))
      (node (ref "J6") (pin "49") (pinfunction "VTT_49") (pintype "passive"))
      (node (ref "R381") (pin "1") (pinfunction "1_1") (pintype "passive"))
      (node (ref "U63") (pin "3") (pinfunction "VTT_3") (pintype "output"))
    )
    (net (code "149") (name "GND") (class "Default")
      (node (ref "C632") (pin "2") (pinfunction "2_2") (pintype "passive"))
      (node (ref "C633") (pin "1") (pinfunction "1_1") (pintype "passive"))
      (node (ref "C634") (pin "1") (pinfunction "1_1") (pintype "passive"))
      (node (ref "C635") (pin "1") (pinfunction "1_1") (pintype "passive"))
      (node (ref "C636") (pin "1") (pinfunction "1_1") (pintype "passive"))
      (node (ref "C637") (pin "1") (pinfunction "1_1") (pintype "passive"))
      (node (ref "C638") (pin "1") (pinfunction "1_1") (pintype "passive"))
      (node (ref "C639") (pin "1") (pinfunction "1_1") (pintype "passive"))
      (node (ref "C640") (pin "1") (pinfunction "1_1") (pintype "passive"))
      (node (ref "C641") (pin "1") (pinfunction "1_1") (pintype "passive"))
      (node (ref "C642") (pin "1") (pinfunction "1_1") (pintype "passive"))
      (node (ref "C643") (pin "1") (pinfunction "1_1") (pintype "passive"))
      (node (ref "C644") (pin "1") (pinfunction "1_1") (pintype "passive"))
      (node (ref "C645") (pin "1") (pinfunction "1_1") (pintype "passive"))
      (node (ref "C646") (pin "1") (pinfunction "1_1") (pintype "passive"))
      (node (ref "C647") (pin "1") (pinfunction "1_1") (pintype "passive"))
      (node (ref "C648") (pin "1") (pinfunction "1_1") (pintype "passive"))
      (node (ref "C649") (pin "1") (pinfunction "1_1") (pintype "passive"))
      (node (ref "C650") (pin "1") (pinfunction "1_1") (pintype "passive"))
      (node (ref "C651") (pin "1") (pinfunction "1_1") (pintype "passive"))
      (node (ref "C652") (pin "1") (pinfunction "1_1") (pintype "passive"))
      (node (ref "C653") (pin "1") (pinfunction "1_1") (pintype "passive"))
      (node (ref "C654") (pin "1") (pinfunction "1_1") (pintype "passive"))
      (node (ref "C655") (pin "1") (pinfunction "1_1") (pintype "passive"))
      (node (ref "C661") (pin "1") (pinfunction "1_1") (pintype "passive"))
      (node (ref "C662") (pin "1") (pinfunction "1_1") (pintype "passive"))
      (node (ref "C663") (pin "1") (pinfunction "1_1") (pintype "passive"))
      (node (ref "C664") (pin "1") (pinfunction "1_1") (pintype "passive"))
      (node (ref "C665") (pin "1") (pinfunction "1_1") (pintype "passive"))
      (node (ref "C666") (pin "1") (pinfunction "1_1") (pintype "passive"))
      (node (ref "C667") (pin "1") (pinfunction "1_1") (pintype "passive"))
      (node (ref "C668") (pin "1") (pinfunction "1_1") (pintype "passive"))
      (node (ref "C669") (pin "1") (pinfunction "1_1") (pintype "passive"))
      (node (ref "C670") (pin "1") (pinfunction "1_1") (pintype "passive"))
      (node (ref "J6") (pin "101") (pinfunction "VSS_101") (pintype "passive"))
      (node (ref "J6") (pin "104") (pinfunction "VSS_104") (pintype "passive"))
      (node (ref "J6") (pin "107") (pinfunction "VSS_107") (pintype "passive"))
      (node (ref "J6") (pin "11") (pinfunction "VSS_11") (pintype "passive"))
      (node (ref "J6") (pin "110") (pinfunction "VSS_110") (pintype "passive"))
      (node (ref "J6") (pin "113") (pinfunction "VSS_113") (pintype "passive"))
      (node (ref "J6") (pin "116") (pinfunction "VSS_116") (pintype "passive"))
      (node (ref "J6") (pin "117") (pinfunction "SA0_117") (pintype "input"))
      (node (ref "J6") (pin "121") (pinfunction "VSS_121") (pintype "passive"))
      (node (ref "J6") (pin "124") (pinfunction "VSS_124") (pintype "passive"))
      (node (ref "J6") (pin "127") (pinfunction "VSS_127") (pintype "passive"))
      (node (ref "J6") (pin "130") (pinfunction "VSS_130") (pintype "passive"))
      (node (ref "J6") (pin "133") (pinfunction "VSS_133") (pintype "passive"))
      (node (ref "J6") (pin "136") (pinfunction "VSS_136") (pintype "passive"))
      (node (ref "J6") (pin "139") (pinfunction "VSS_139") (pintype "passive"))
      (node (ref "J6") (pin "14") (pinfunction "VSS_14") (pintype "passive"))
      (node (ref "J6") (pin "142") (pinfunction "VSS_142") (pintype "passive"))
      (node (ref "J6") (pin "145") (pinfunction "VSS_145") (pintype "passive"))
      (node (ref "J6") (pin "148") (pinfunction "VSS_148") (pintype "passive"))
      (node (ref "J6") (pin "151") (pinfunction "VSS_151") (pintype "passive"))
      (node (ref "J6") (pin "154") (pinfunction "VSS_154") (pintype "passive"))
      (node (ref "J6") (pin "157") (pinfunction "VSS_157") (pintype "passive"))
      (node (ref "J6") (pin "160") (pinfunction "VSS_160") (pintype "passive"))
      (node (ref "J6") (pin "163") (pinfunction "VSS_163") (pintype "passive"))
      (node (ref "J6") (pin "166") (pinfunction "VSS_166") (pintype "passive"))
      (node (ref "J6") (pin "17") (pinfunction "VSS_17") (pintype "passive"))
      (node (ref "J6") (pin "199") (pinfunction "VSS_199") (pintype "passive"))
      (node (ref "J6") (pin "2") (pinfunction "VSS_2") (pintype "passive"))
      (node (ref "J6") (pin "20") (pinfunction "VSS_20") (pintype "passive"))
      (node (ref "J6") (pin "202") (pinfunction "VSS_202") (pintype "passive"))
      (node (ref "J6") (pin "205") (pinfunction "VSS_205") (pintype "passive"))
      (node (ref "J6") (pin "208") (pinfunction "VSS_208") (pintype "passive"))
      (node (ref "J6") (pin "211") (pinfunction "VSS_211") (pintype "passive"))
      (node (ref "J6") (pin "214") (pinfunction "VSS_214") (pintype "passive"))
      (node (ref "J6") (pin "217") (pinfunction "VSS_217") (pintype "passive"))
      (node (ref "J6") (pin "220") (pinfunction "VSS_220") (pintype "passive"))
      (node (ref "J6") (pin "223") (pinfunction "VSS_223") (pintype "passive"))
      (node (ref "J6") (pin "226") (pinfunction "VSS_226") (pintype "passive"))
      (node (ref "J6") (pin "229") (pinfunction "VSS_229") (pintype "passive"))
      (node (ref "J6") (pin "23") (pinfunction "VSS_23") (pintype "passive"))
      (node (ref "J6") (pin "232") (pinfunction "VSS_232") (pintype "passive"))
      (node (ref "J6") (pin "235") (pinfunction "VSS_235") (pintype "passive"))
      (node (ref "J6") (pin "239") (pinfunction "VSS_239") (pintype "passive"))
      (node (ref "J6") (pin "26") (pinfunction "VSS_26") (pintype "passive"))
      (node (ref "J6") (pin "29") (pinfunction "VSS_29") (pintype "passive"))
      (node (ref "J6") (pin "32") (pinfunction "VSS_32") (pintype "passive"))
      (node (ref "J6") (pin "35") (pinfunction "VSS_35") (pintype "passive"))
      (node (ref "J6") (pin "38") (pinfunction "VSS_38") (pintype "passive"))
      (node (ref "J6") (pin "41") (pinfunction "VSS_41") (pintype "passive"))
      (node (ref "J6") (pin "44") (pinfunction "VSS_44") (pintype "passive"))
      (node (ref "J6") (pin "47") (pinfunction "VSS_47") (pintype "passive"))
      (node (ref "J6") (pin "5") (pinfunction "VSS_5") (pintype "passive"))
      (node (ref "J6") (pin "8") (pinfunction "VSS_8") (pintype "passive"))
      (node (ref "J6") (pin "80") (pinfunction "VSS_80") (pintype "passive"))
      (node (ref "J6") (pin "83") (pinfunction "VSS_83") (pintype "passive"))
      (node (ref "J6") (pin "86") (pinfunction "VSS_86") (pintype "passive"))
      (node (ref "J6") (pin "89") (pinfunction "VSS_89") (pintype "passive"))
      (node (ref "J6") (pin "92") (pinfunction "VSS_92") (pintype "passive"))
      (node (ref "J6") (pin "95") (pinfunction "VSS_95") (pintype "passive"))
      (node (ref "J6") (pin "98") (pinfunction "VSS_98") (pintype "passive"))
      (node (ref "U63") (pin "11") (pinfunction "PPAD_11") (pintype "passive"))
      (node (ref "U63") (pin "4") (pinfunction "PGND_4") (pintype "passive"))
      (node (ref "U63") (pin "8") (pinfunction "GND_8") (pintype "passive"))
    )
    (net (code "150") (name "Net-(J6B-CK1_c)") (class "Default")
      (node (ref "J6") (pin "64") (pinfunction "CK1_c_64") (pintype "input"))
      (node (ref "TP25") (pin "1") (pinfunction "1_1") (pintype "passive"))
    )
    (net (code "151") (name "Net-(J6B-CK1_t)") (class "Default")
      (node (ref "J6") (pin "63") (pinfunction "CK1_t_63") (pintype "input"))
      (node (ref "TP24") (pin "1") (pinfunction "1_1") (pintype "passive"))
    )
    (net (code "152") (name "Net-(J6B-EVENT_n)") (class "Default")
      (node (ref "J6") (pin "187") (pinfunction "EVENT_n_187") (pintype "output"))
      (node (ref "TP30") (pin "1") (pinfunction "1_1") (pintype "passive"))
    )
    (net (code "153") (name "Net-(J6B-Err_Out_n)") (class "Default")
      (node (ref "J6") (pin "53") (pinfunction "Err_Out_n_53") (pintype "output"))
      (node (ref "TP27") (pin "1") (pinfunction "1_1") (pintype "passive"))
    )
    (net (code "154") (name "Net-(J6B-Par_In)") (class "Default")
      (node (ref "J6") (pin "68") (pinfunction "Par_In_68") (pintype "input"))
      (node (ref "TP26") (pin "1") (pinfunction "1_1") (pintype "passive"))
    )
    (net (code "155") (name "Net-(J6B-SCL)") (class "Default")
      (node (ref "J6") (pin "118") (pinfunction "SCL_118") (pintype "input"))
      (node (ref "R377") (pin "1") (pinfunction "1_1") (pintype "passive"))
      (node (ref "R378") (pin "1") (pinfunction "1_1") (pintype "passive"))
    )
    (net (code "156") (name "Net-(J6B-SDA)") (class "Default")
      (node (ref "J6") (pin "238") (pinfunction "SDA_238") (pintype "input"))
      (node (ref "R376") (pin "1") (pinfunction "1_1") (pintype "passive"))
      (node (ref "R379") (pin "1") (pinfunction "1_1") (pintype "passive"))
    )
    (net (code "157") (name "Net-(U63-S3)") (class "Default")
      (node (ref "R380") (pin "2") (pinfunction "2_2") (pintype "passive"))
      (node (ref "U63") (pin "7") (pinfunction "S3_7") (pintype "input"))
    )
    (net (code "158") (name "Net-(U63-S5)") (class "Default")
      (node (ref "R382") (pin "2") (pinfunction "2_2") (pintype "passive"))
      (node (ref "U63") (pin "9") (pinfunction "S5_9") (pintype "input"))
    )
    (net (code "159") (name "Net-(U63-VTTSNS)") (class "Default")
      (node (ref "C665") (pin "2") (pinfunction "2_2") (pintype "passive"))
      (node (ref "R381") (pin "2") (pinfunction "2_2") (pintype "passive"))
      (node (ref "U63") (pin "5") (pinfunction "VTTSNS_5") (pintype "input"))
    )
    (net (code "160") (name "unconnected-(J6B-TEST-Pad167)") (class "Default")
      (node (ref "J6") (pin "167") (pinfunction "TEST_167") (pintype "output+no_connect"))
    )
    (net (code "161") (name "unconnected-(J6E-NC-Pad126)") (class "Default")
      (node (ref "J6") (pin "126") (pinfunction "NC_126") (pintype "passive+no_connect"))
    )
    (net (code "162") (name "unconnected-(J6E-NC-Pad135)") (class "Default")
      (node (ref "J6") (pin "135") (pinfunction "NC_135") (pintype "passive+no_connect"))
    )
    (net (code "163") (name "unconnected-(J6E-NC-Pad144)") (class "Default")
      (node (ref "J6") (pin "144") (pinfunction "NC_144") (pintype "passive+no_connect"))
    )
    (net (code "164") (name "unconnected-(J6E-NC-Pad153)") (class "Default")
      (node (ref "J6") (pin "153") (pinfunction "NC_153") (pintype "passive+no_connect"))
    )
    (net (code "165") (name "unconnected-(J6E-NC-Pad162)") (class "Default")
      (node (ref "J6") (pin "162") (pinfunction "NC_162") (pintype "passive+no_connect"))
    )
    (net (code "166") (name "unconnected-(J6E-NC-Pad204)") (class "Default")
      (node (ref "J6") (pin "204") (pinfunction "NC_204") (pintype "passive+no_connect"))
    )
    (net (code "167") (name "unconnected-(J6E-NC-Pad213)") (class "Default")
      (node (ref "J6") (pin "213") (pinfunction "NC_213") (pintype "passive+no_connect"))
    )
    (net (code "168") (name "unconnected-(J6E-NC-Pad222)") (class "Default")
      (node (ref "J6") (pin "222") (pinfunction "NC_222") (pintype "passive+no_connect"))
    )
    (net (code "169") (name "unconnected-(J6E-NC-Pad231)") (class "Default")
      (node (ref "J6") (pin "231") (pinfunction "NC_231") (pintype "passive+no_connect"))
    )
  )
)
